# Modulo_Telemetros.net
KiCad netlist of a schematic drawn in Altium Designer
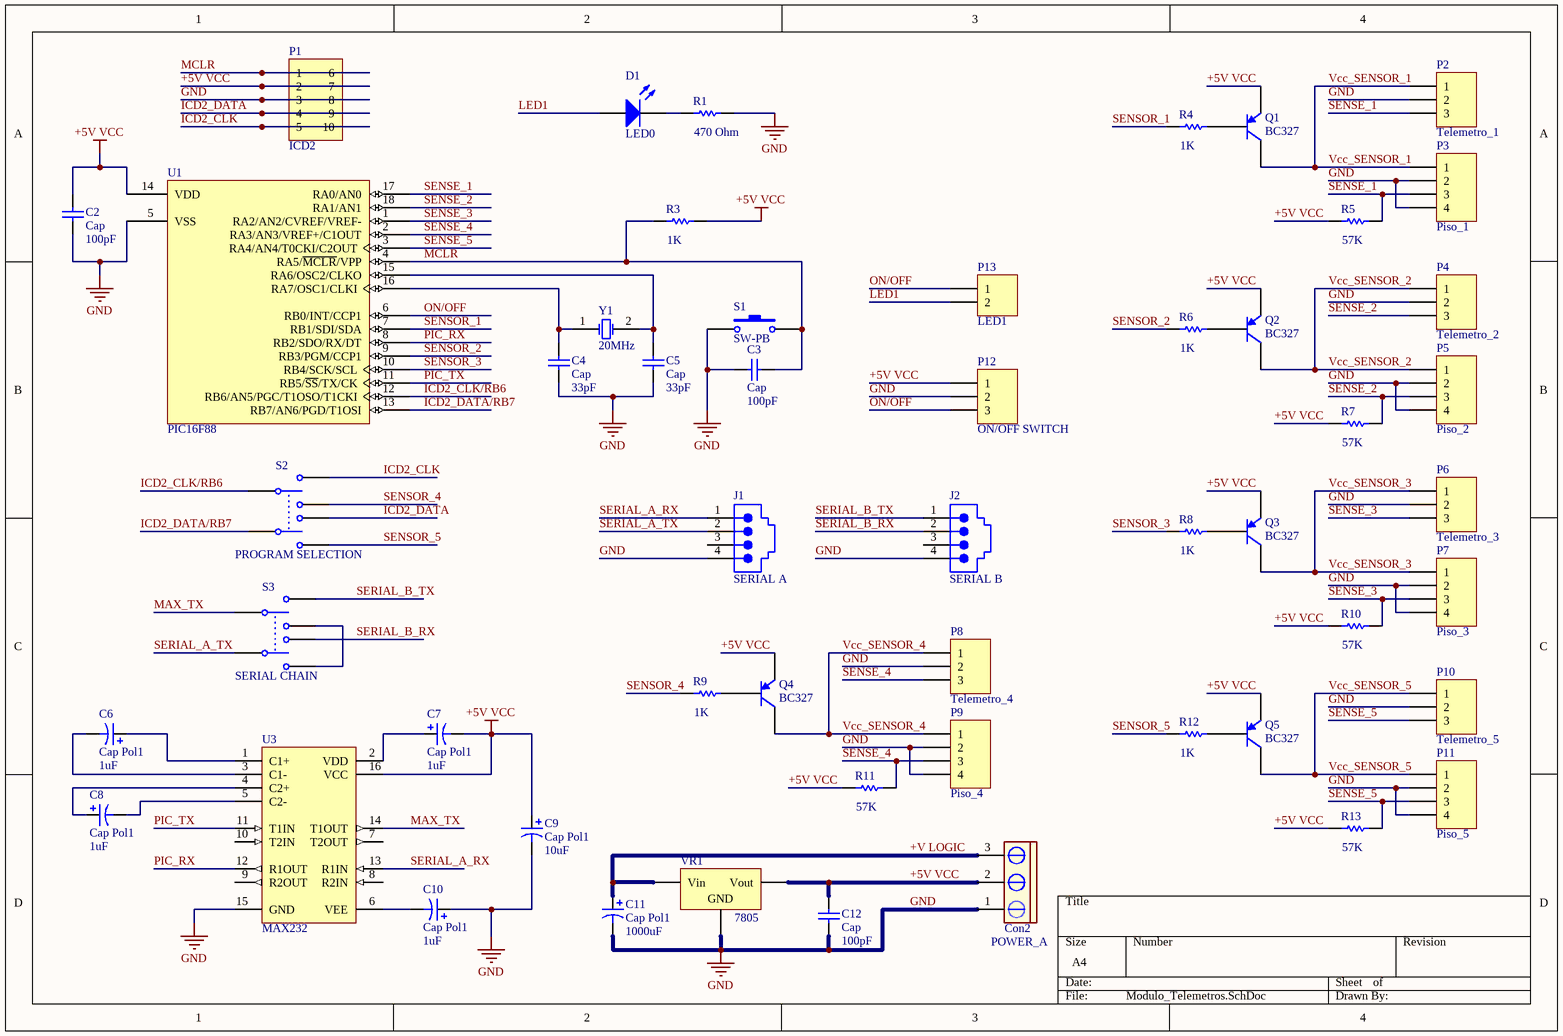
[diagram p0: Modulo_Telemetros.SchDoc]

(export (version "E")
  (design (tool "Eeschema 10.0.6"))
  (components
    (comp (ref "C2")
      (value "Cap")
      (footprint "CAPR2.54-5.1x3.2")
      (description "Capacitor")
      (fields (field (name "ALTIUM_VALUE") "100pF") (field (name "PUBLISHER") "Altium Limited"))
      (libsource (lib "Miscellaneous Devices") (part "Cap"))
    )
    (comp (ref "C3")
      (value "Cap")
      (footprint "CAPR2.54-5.1x3.2")
      (description "Capacitor")
      (fields (field (name "ALTIUM_VALUE") "100pF") (field (name "PUBLISHER") "Altium Limited"))
      (libsource (lib "Miscellaneous Devices") (part "Cap"))
    )
    (comp (ref "C4")
      (value "Cap")
      (footprint "CAPR2.54-5.1x3.2")
      (description "Capacitor")
      (fields (field (name "ALTIUM_VALUE") "33pF") (field (name "PUBLISHER") "Altium Limited"))
      (libsource (lib "Miscellaneous Devices") (part "Cap"))
    )
    (comp (ref "C5")
      (value "Cap")
      (footprint "CAPR2.54-5.1x3.2")
      (description "Capacitor")
      (fields (field (name "ALTIUM_VALUE") "33pF") (field (name "PUBLISHER") "Altium Limited"))
      (libsource (lib "Miscellaneous Devices") (part "Cap"))
    )
    (comp (ref "C6")
      (value "Cap Pol1")
      (footprint "CAPPR2-5x6.8")
      (description "Polarized Capacitor (Radial)")
      (fields (field (name "ALTIUM_VALUE") "1uF") (field (name "PUBLISHER") "Altium Limited"))
      (libsource (lib "Miscellaneous Devices") (part "Cap Pol1"))
    )
    (comp (ref "C7")
      (value "Cap Pol1")
      (footprint "CAPPR2-5x6.8")
      (description "Polarized Capacitor (Radial)")
      (fields (field (name "ALTIUM_VALUE") "1uF") (field (name "PUBLISHER") "Altium Limited"))
      (libsource (lib "Miscellaneous Devices") (part "Cap Pol1"))
    )
    (comp (ref "C8")
      (value "Cap Pol1")
      (footprint "CAPPR2-5x6.8")
      (description "Polarized Capacitor (Radial)")
      (fields (field (name "ALTIUM_VALUE") "1uF") (field (name "PUBLISHER") "Altium Limited"))
      (libsource (lib "Miscellaneous Devices") (part "Cap Pol1"))
    )
    (comp (ref "C9")
      (value "Cap Pol1")
      (footprint "CAPPR2-5x6.8")
      (description "Polarized Capacitor (Radial)")
      (fields (field (name "ALTIUM_VALUE") "10uF") (field (name "PUBLISHER") "Altium Limited"))
      (libsource (lib "Miscellaneous Devices") (part "Cap Pol1"))
    )
    (comp (ref "C10")
      (value "Cap Pol1")
      (footprint "CAPPR2-5x6.8")
      (description "Polarized Capacitor (Radial)")
      (fields (field (name "ALTIUM_VALUE") "1uF") (field (name "PUBLISHER") "Altium Limited"))
      (libsource (lib "Miscellaneous Devices") (part "Cap Pol1"))
    )
    (comp (ref "C11")
      (value "Cap Pol1")
      (footprint "RB5-10.5")
      (description "Polarized Capacitor (Radial)")
      (fields (field (name "ALTIUM_VALUE") "1000uF") (field (name "PUBLISHER") "Altium Limited"))
      (libsource (lib "Miscellaneous Devices") (part "Cap Pol1"))
    )
    (comp (ref "C12")
      (value "Cap")
      (footprint "CAPR2.54-5.1x3.2")
      (description "Capacitor")
      (fields (field (name "ALTIUM_VALUE") "100pF") (field (name "PUBLISHER") "Altium Limited"))
      (libsource (lib "Miscellaneous Devices") (part "Cap"))
    )
    (comp (ref "Con2")
      (value "POWER_A")
      (footprint "My_CN3")
      (description "Connector green screw")
      (libsource (lib "Protel_Library") (part "CON3 pin Green"))
    )
    (comp (ref "D1")
      (value "LED0")
      (footprint "LED-0")
      (description "Typical INFRARED GaAs LED")
      (fields (field (name "PUBLISHER") "Altium Limited"))
      (libsource (lib "Miscellaneous Devices") (part "LED0"))
    )
    (comp (ref "J1")
      (value "SERIAL A")
      (footprint "15-43-6245")
      (description "Right Angle, Standard Profile, RJ45-Keyed, Flange Mount PCB Jack")
      (fields (field (name "PUBLISHER") "Altium Limited"))
      (libsource (lib "Molex Modular Jack Right Angle") (part "15-43-6245"))
    )
    (comp (ref "J2")
      (value "SERIAL B")
      (footprint "15-43-6245")
      (description "Right Angle, Standard Profile, RJ45-Keyed, Flange Mount PCB Jack")
      (fields (field (name "PUBLISHER") "Altium Limited"))
      (libsource (lib "Molex Modular Jack Right Angle") (part "15-43-6245"))
    )
    (comp (ref "P1")
      (value "ICD2")
      (footprint "HEADER10_5x2_B")
      (description "Header, 5-Pin, Dual row")
      (fields (field (name "PUBLISHER") "Altium Limited"))
      (libsource (lib "Miscellaneous Connectors") (part "Header 5X2A"))
    )
    (comp (ref "P2")
      (value "Telemetro_1")
      (footprint "HDR1X3")
      (description "Header, 3-Pin")
      (fields (field (name "PUBLISHER") "Altium Limited"))
      (libsource (lib "Miscellaneous Connectors") (part "Header 3"))
    )
    (comp (ref "P3")
      (value "Piso_1")
      (footprint "HDR1X4")
      (description "Header, 4-Pin")
      (fields (field (name "PUBLISHER") "Altium Limited"))
      (libsource (lib "Miscellaneous Connectors") (part "Header 4"))
    )
    (comp (ref "P4")
      (value "Telemetro_2")
      (footprint "HDR1X3")
      (description "Header, 3-Pin")
      (fields (field (name "PUBLISHER") "Altium Limited"))
      (libsource (lib "Miscellaneous Connectors") (part "Header 3"))
    )
    (comp (ref "P5")
      (value "Piso_2")
      (footprint "HDR1X4")
      (description "Header, 4-Pin")
      (fields (field (name "PUBLISHER") "Altium Limited"))
      (libsource (lib "Miscellaneous Connectors") (part "Header 4"))
    )
    (comp (ref "P6")
      (value "Telemetro_3")
      (footprint "HDR1X3")
      (description "Header, 3-Pin")
      (fields (field (name "PUBLISHER") "Altium Limited"))
      (libsource (lib "Miscellaneous Connectors") (part "Header 3"))
    )
    (comp (ref "P7")
      (value "Piso_3")
      (footprint "HDR1X4")
      (description "Header, 4-Pin")
      (fields (field (name "PUBLISHER") "Altium Limited"))
      (libsource (lib "Miscellaneous Connectors") (part "Header 4"))
    )
    (comp (ref "P8")
      (value "Telemetro_4")
      (footprint "HDR1X3")
      (description "Header, 3-Pin")
      (fields (field (name "PUBLISHER") "Altium Limited"))
      (libsource (lib "Miscellaneous Connectors") (part "Header 3"))
    )
    (comp (ref "P9")
      (value "Piso_4")
      (footprint "HDR1X4")
      (description "Header, 4-Pin")
      (fields (field (name "PUBLISHER") "Altium Limited"))
      (libsource (lib "Miscellaneous Connectors") (part "Header 4"))
    )
    (comp (ref "P10")
      (value "Telemetro_5")
      (footprint "HDR1X3")
      (description "Header, 3-Pin")
      (fields (field (name "PUBLISHER") "Altium Limited"))
      (libsource (lib "Miscellaneous Connectors") (part "Header 3"))
    )
    (comp (ref "P11")
      (value "Piso_5")
      (footprint "HDR1X4")
      (description "Header, 4-Pin")
      (fields (field (name "PUBLISHER") "Altium Limited"))
      (libsource (lib "Miscellaneous Connectors") (part "Header 4"))
    )
    (comp (ref "P12")
      (value "ON/OFF SWITCH")
      (footprint "HDR1X3")
      (description "Header, 3-Pin")
      (fields (field (name "PUBLISHER") "Altium Limited"))
      (libsource (lib "Miscellaneous Connectors") (part "Header 3"))
    )
    (comp (ref "P13")
      (value "LED1")
      (footprint "HDR1X2")
      (description "Header, 2-Pin")
      (fields (field (name "PUBLISHER") "Altium Limited"))
      (libsource (lib "Miscellaneous Connectors") (part "Header 2"))
    )
    (comp (ref "Q1")
      (value "BC327")
      (footprint "TO-92A")
      (description "PNP Switching Transistor")
      (fields (field (name "PUBLISHER") "Altium Limited"))
      (libsource (lib "FSC Discrete BJT") (part "2N5771"))
    )
    (comp (ref "Q2")
      (value "BC327")
      (footprint "TO-92A")
      (description "PNP Switching Transistor")
      (fields (field (name "PUBLISHER") "Altium Limited"))
      (libsource (lib "FSC Discrete BJT") (part "2N5771"))
    )
    (comp (ref "Q3")
      (value "BC327")
      (footprint "TO-92A")
      (description "PNP Switching Transistor")
      (fields (field (name "PUBLISHER") "Altium Limited"))
      (libsource (lib "FSC Discrete BJT") (part "2N5771"))
    )
    (comp (ref "Q4")
      (value "BC327")
      (footprint "TO-92A")
      (description "PNP Switching Transistor")
      (fields (field (name "PUBLISHER") "Altium Limited"))
      (libsource (lib "FSC Discrete BJT") (part "2N5771"))
    )
    (comp (ref "Q5")
      (value "BC327")
      (footprint "TO-92A")
      (description "PNP Switching Transistor")
      (fields (field (name "PUBLISHER") "Altium Limited"))
      (libsource (lib "FSC Discrete BJT") (part "2N5771"))
    )
    (comp (ref "R1")
      (value "470 Ohm")
      (footprint "AXIAL-0.3")
      (description "Resistor")
      (fields (field (name "Comment") "Res1") (field (name "PUBLISHER") "Altium Limited"))
      (libsource (lib "Miscellaneous Devices") (part "Res1"))
    )
    (comp (ref "R3")
      (value "1K")
      (footprint "AXIAL-0.3")
      (description "Resistor")
      (fields (field (name "Comment") "Res1") (field (name "PUBLISHER") "Altium Limited"))
      (libsource (lib "Miscellaneous Devices") (part "Res1"))
    )
    (comp (ref "R4")
      (value "1K")
      (footprint "AXIAL-0.3")
      (description "Resistor")
      (fields (field (name "Comment") "Res1") (field (name "PUBLISHER") "Altium Limited"))
      (libsource (lib "Miscellaneous Devices") (part "Res1"))
    )
    (comp (ref "R5")
      (value "57K")
      (footprint "AXIAL-0.3")
      (description "Resistor")
      (fields (field (name "Comment") "Res1") (field (name "PUBLISHER") "Altium Limited"))
      (libsource (lib "Miscellaneous Devices") (part "Res1"))
    )
    (comp (ref "R6")
      (value "1K")
      (footprint "AXIAL-0.3")
      (description "Resistor")
      (fields (field (name "Comment") "Res1") (field (name "PUBLISHER") "Altium Limited"))
      (libsource (lib "Miscellaneous Devices") (part "Res1"))
    )
    (comp (ref "R7")
      (value "57K")
      (footprint "AXIAL-0.3")
      (description "Resistor")
      (fields (field (name "Comment") "Res1") (field (name "PUBLISHER") "Altium Limited"))
      (libsource (lib "Miscellaneous Devices") (part "Res1"))
    )
    (comp (ref "R8")
      (value "1K")
      (footprint "AXIAL-0.3")
      (description "Resistor")
      (fields (field (name "Comment") "Res1") (field (name "PUBLISHER") "Altium Limited"))
      (libsource (lib "Miscellaneous Devices") (part "Res1"))
    )
    (comp (ref "R9")
      (value "1K")
      (footprint "AXIAL-0.3")
      (description "Resistor")
      (fields (field (name "Comment") "Res1") (field (name "PUBLISHER") "Altium Limited"))
      (libsource (lib "Miscellaneous Devices") (part "Res1"))
    )
    (comp (ref "R10")
      (value "57K")
      (footprint "AXIAL-0.3")
      (description "Resistor")
      (fields (field (name "Comment") "Res1") (field (name "PUBLISHER") "Altium Limited"))
      (libsource (lib "Miscellaneous Devices") (part "Res1"))
    )
    (comp (ref "R11")
      (value "57K")
      (footprint "AXIAL-0.3")
      (description "Resistor")
      (fields (field (name "Comment") "Res1") (field (name "PUBLISHER") "Altium Limited"))
      (libsource (lib "Miscellaneous Devices") (part "Res1"))
    )
    (comp (ref "R12")
      (value "1K")
      (footprint "AXIAL-0.3")
      (description "Resistor")
      (fields (field (name "Comment") "Res1") (field (name "PUBLISHER") "Altium Limited"))
      (libsource (lib "Miscellaneous Devices") (part "Res1"))
    )
    (comp (ref "R13")
      (value "57K")
      (footprint "AXIAL-0.3")
      (description "Resistor")
      (fields (field (name "Comment") "Res1") (field (name "PUBLISHER") "Altium Limited"))
      (libsource (lib "Miscellaneous Devices") (part "Res1"))
    )
    (comp (ref "S1")
      (value "SW-PB")
      (footprint "TS-063")
      (description "Switch")
      (fields (field (name "PUBLISHER") "Altium Limited"))
      (libsource (lib "Miscellaneous Devices") (part "SW-PB"))
    )
    (comp (ref "S2")
      (value "PROGRAM SELECTION")
      (footprint "LD-202mini")
      (description "Double-Pole, Double-Throw Switch")
      (fields (field (name "PUBLISHER") "Altium Limited"))
      (libsource (lib "Miscellaneous Devices") (part "SW-DPDT"))
    )
    (comp (ref "S3")
      (value "SERIAL CHAIN")
      (footprint "LD-202mini")
      (description "Double-Pole, Double-Throw Switch")
      (fields (field (name "PUBLISHER") "Altium Limited"))
      (libsource (lib "Miscellaneous Devices") (part "SW-DPDT"))
    )
    (comp (ref "U1")
      (value "PIC16F88")
      (footprint "PDIP300-P18")
      (fields (field (name "PUBLISHER") "Altium Limited"))
      (libsource (lib "Microchip Microcontroller 8-Bit PIC16") (part "PIC16F88-E/P"))
    )
    (comp (ref "U3")
      (value "MAX232")
      (footprint "PE16A")
      (description "+5V Powered, Multi-Channel RS-232 Driver/Receiver")
      (fields (field (name "PUBLISHER") "Altium Limited"))
      (libsource (lib "Maxim Communication Transceiver") (part "MAX232ACPE"))
    )
    (comp (ref "VR1")
      (value "7805")
      (footprint "My_TO-220")
      (description "Voltage Regulator")
      (fields (field (name "PUBLISHER") "Altium Limited"))
      (libsource (lib "Miscellaneous Devices") (part "Volt Reg"))
    )
    (comp (ref "Y1")
      (value "20MHz")
      (footprint "My_Crystal")
      (description "Crystal Oscillator")
      (fields (field (name "PUBLISHER") "Altium Limited"))
      (libsource (lib "Miscellaneous Devices") (part "XTAL"))
    )
  )
  (nets
    (net (code "1") (name "+5V VCC") (class "Default")
      (node (ref "C12") (pin "2") (pinfunction "2_2") (pintype "passive"))
      (node (ref "C2") (pin "2") (pinfunction "2_2") (pintype "passive"))
      (node (ref "C7") (pin "2") (pinfunction "2_2") (pintype "passive"))
      (node (ref "C9") (pin "1") (pinfunction "1_1") (pintype "passive"))
      (node (ref "Con2") (pin "2") (pinfunction "2_2") (pintype "passive"))
      (node (ref "P1") (pin "2") (pinfunction "2_2") (pintype "passive"))
      (node (ref "P1") (pin "7") (pinfunction "7_7") (pintype "passive"))
      (node (ref "P12") (pin "1") (pinfunction "1_1") (pintype "passive"))
      (node (ref "Q1") (pin "1") (pinfunction "E_1") (pintype "passive"))
      (node (ref "Q2") (pin "1") (pinfunction "E_1") (pintype "passive"))
      (node (ref "Q3") (pin "1") (pinfunction "E_1") (pintype "passive"))
      (node (ref "Q4") (pin "1") (pinfunction "E_1") (pintype "passive"))
      (node (ref "Q5") (pin "1") (pinfunction "E_1") (pintype "passive"))
      (node (ref "R10") (pin "1") (pinfunction "1_1") (pintype "passive"))
      (node (ref "R11") (pin "1") (pinfunction "1_1") (pintype "passive"))
      (node (ref "R13") (pin "1") (pinfunction "1_1") (pintype "passive"))
      (node (ref "R3") (pin "2") (pinfunction "2_2") (pintype "passive"))
      (node (ref "R5") (pin "1") (pinfunction "1_1") (pintype "passive"))
      (node (ref "R7") (pin "1") (pinfunction "1_1") (pintype "passive"))
      (node (ref "U1") (pin "14") (pinfunction "VDD_14") (pintype "power_in"))
      (node (ref "U3") (pin "16") (pinfunction "VCC_16") (pintype "power_in"))
      (node (ref "VR1") (pin "3") (pinfunction "Vout_3") (pintype "passive"))
    )
    (net (code "2") (name "/+V LOGIC") (class "Default")
      (node (ref "C11") (pin "1") (pinfunction "1_1") (pintype "passive"))
      (node (ref "Con2") (pin "3") (pinfunction "3_3") (pintype "passive"))
      (node (ref "VR1") (pin "1") (pinfunction "Vin_1") (pintype "passive"))
    )
    (net (code "3") (name "/ICD2_CLK") (class "Default")
      (node (ref "P1") (pin "10") (pinfunction "10_10") (pintype "passive"))
      (node (ref "P1") (pin "5") (pinfunction "5_5") (pintype "passive"))
      (node (ref "S2") (pin "2") (pinfunction "2_2") (pintype "passive"))
    )
    (net (code "4") (name "/ICD2_CLK{slash}RB6") (class "Default")
      (node (ref "S2") (pin "1") (pinfunction "1_1") (pintype "passive"))
      (node (ref "U1") (pin "12") (pinfunction "RB6/AN5/PGC/T1OSO/T1CKI_12") (pintype "bidirectional"))
    )
    (net (code "5") (name "/ICD2_DATA") (class "Default")
      (node (ref "P1") (pin "4") (pinfunction "4_4") (pintype "passive"))
      (node (ref "P1") (pin "9") (pinfunction "9_9") (pintype "passive"))
      (node (ref "S2") (pin "5") (pinfunction "5_5") (pintype "passive"))
    )
    (net (code "6") (name "/ICD2_DATA{slash}RB7") (class "Default")
      (node (ref "S2") (pin "4") (pinfunction "4_4") (pintype "passive"))
      (node (ref "U1") (pin "13") (pinfunction "RB7/AN6/PGD/T1OSI_13") (pintype "bidirectional"))
    )
    (net (code "7") (name "/LED1") (class "Default")
      (node (ref "D1") (pin "1") (pinfunction "A_1") (pintype "passive"))
      (node (ref "P13") (pin "2") (pinfunction "2_2") (pintype "passive"))
    )
    (net (code "8") (name "/MAX_TX") (class "Default")
      (node (ref "S3") (pin "1") (pinfunction "1_1") (pintype "passive"))
      (node (ref "U3") (pin "14") (pinfunction "T1OUT_14") (pintype "output"))
    )
    (net (code "9") (name "/MCLR") (class "Default")
      (node (ref "C3") (pin "2") (pinfunction "2_2") (pintype "passive"))
      (node (ref "P1") (pin "1") (pinfunction "1_1") (pintype "passive"))
      (node (ref "P1") (pin "6") (pinfunction "6_6") (pintype "passive"))
      (node (ref "R3") (pin "1") (pinfunction "1_1") (pintype "passive"))
      (node (ref "S1") (pin "2") (pinfunction "2_2") (pintype "passive"))
      (node (ref "U1") (pin "4") (pinfunction "RA5/~{MCLR}/VPP_4") (pintype "bidirectional"))
    )
    (net (code "10") (name "/ON{slash}OFF") (class "Default")
      (node (ref "P12") (pin "3") (pinfunction "3_3") (pintype "passive"))
      (node (ref "P13") (pin "1") (pinfunction "1_1") (pintype "passive"))
      (node (ref "U1") (pin "6") (pinfunction "RB0/INT/CCP1_6") (pintype "bidirectional"))
    )
    (net (code "11") (name "/PIC_RX") (class "Default")
      (node (ref "U1") (pin "8") (pinfunction "RB2/SDO/RX/DT_8") (pintype "bidirectional"))
      (node (ref "U3") (pin "12") (pinfunction "R1OUT_12") (pintype "output"))
    )
    (net (code "12") (name "/PIC_TX") (class "Default")
      (node (ref "U1") (pin "11") (pinfunction "RB5/~{SS}/TX/CK_11") (pintype "bidirectional"))
      (node (ref "U3") (pin "11") (pinfunction "T1IN_11") (pintype "input"))
    )
    (net (code "13") (name "/SENSE_1") (class "Default")
      (node (ref "P2") (pin "3") (pinfunction "3_3") (pintype "passive"))
      (node (ref "P3") (pin "3") (pinfunction "3_3") (pintype "passive"))
      (node (ref "R5") (pin "2") (pinfunction "2_2") (pintype "passive"))
      (node (ref "U1") (pin "17") (pinfunction "RA0/AN0_17") (pintype "bidirectional"))
    )
    (net (code "14") (name "/SENSE_2") (class "Default")
      (node (ref "P4") (pin "3") (pinfunction "3_3") (pintype "passive"))
      (node (ref "P5") (pin "3") (pinfunction "3_3") (pintype "passive"))
      (node (ref "R7") (pin "2") (pinfunction "2_2") (pintype "passive"))
      (node (ref "U1") (pin "18") (pinfunction "RA1/AN1_18") (pintype "bidirectional"))
    )
    (net (code "15") (name "/SENSE_3") (class "Default")
      (node (ref "P6") (pin "3") (pinfunction "3_3") (pintype "passive"))
      (node (ref "P7") (pin "3") (pinfunction "3_3") (pintype "passive"))
      (node (ref "R10") (pin "2") (pinfunction "2_2") (pintype "passive"))
      (node (ref "U1") (pin "1") (pinfunction "RA2/AN2/CVREF/VREF-_1") (pintype "bidirectional"))
    )
    (net (code "16") (name "/SENSE_4") (class "Default")
      (node (ref "P8") (pin "3") (pinfunction "3_3") (pintype "passive"))
      (node (ref "P9") (pin "3") (pinfunction "3_3") (pintype "passive"))
      (node (ref "R11") (pin "2") (pinfunction "2_2") (pintype "passive"))
      (node (ref "U1") (pin "2") (pinfunction "RA3/AN3/VREF+/C1OUT_2") (pintype "bidirectional"))
    )
    (net (code "17") (name "/SENSE_5") (class "Default")
      (node (ref "P10") (pin "3") (pinfunction "3_3") (pintype "passive"))
      (node (ref "P11") (pin "3") (pinfunction "3_3") (pintype "passive"))
      (node (ref "R13") (pin "2") (pinfunction "2_2") (pintype "passive"))
      (node (ref "U1") (pin "3") (pinfunction "RA4/AN4/T0CKI/C2OUT_3") (pintype "bidirectional"))
    )
    (net (code "18") (name "/SENSOR_1") (class "Default")
      (node (ref "R4") (pin "1") (pinfunction "1_1") (pintype "passive"))
      (node (ref "U1") (pin "7") (pinfunction "RB1/SDI/SDA_7") (pintype "bidirectional"))
    )
    (net (code "19") (name "/SENSOR_2") (class "Default")
      (node (ref "R6") (pin "1") (pinfunction "1_1") (pintype "passive"))
      (node (ref "U1") (pin "9") (pinfunction "RB3/PGM/CCP1_9") (pintype "bidirectional"))
    )
    (net (code "20") (name "/SENSOR_3") (class "Default")
      (node (ref "R8") (pin "1") (pinfunction "1_1") (pintype "passive"))
      (node (ref "U1") (pin "10") (pinfunction "RB4/SCK/SCL_10") (pintype "bidirectional"))
    )
    (net (code "21") (name "/SENSOR_4") (class "Default")
      (node (ref "R9") (pin "1") (pinfunction "1_1") (pintype "passive"))
      (node (ref "S2") (pin "3") (pinfunction "3_3") (pintype "passive"))
    )
    (net (code "22") (name "/SENSOR_5") (class "Default")
      (node (ref "R12") (pin "1") (pinfunction "1_1") (pintype "passive"))
      (node (ref "S2") (pin "6") (pinfunction "6_6") (pintype "passive"))
    )
    (net (code "23") (name "/SERIAL_A_RX") (class "Default")
      (node (ref "J1") (pin "1") (pinfunction "1_1") (pintype "passive"))
      (node (ref "U3") (pin "13") (pinfunction "R1IN_13") (pintype "input"))
    )
    (net (code "24") (name "/SERIAL_A_TX") (class "Default")
      (node (ref "J1") (pin "2") (pinfunction "2_2") (pintype "passive"))
      (node (ref "S3") (pin "4") (pinfunction "4_4") (pintype "passive"))
    )
    (net (code "25") (name "/SERIAL_B_RX") (class "Default")
      (node (ref "J2") (pin "2") (pinfunction "2_2") (pintype "passive"))
      (node (ref "S3") (pin "5") (pinfunction "5_5") (pintype "passive"))
    )
    (net (code "26") (name "/SERIAL_B_TX") (class "Default")
      (node (ref "J2") (pin "1") (pinfunction "1_1") (pintype "passive"))
      (node (ref "S3") (pin "2") (pinfunction "2_2") (pintype "passive"))
    )
    (net (code "27") (name "/Vcc_SENSOR_1") (class "Default")
      (node (ref "P2") (pin "1") (pinfunction "1_1") (pintype "passive"))
      (node (ref "P3") (pin "1") (pinfunction "1_1") (pintype "passive"))
      (node (ref "Q1") (pin "3") (pinfunction "C_3") (pintype "passive"))
    )
    (net (code "28") (name "/Vcc_SENSOR_2") (class "Default")
      (node (ref "P4") (pin "1") (pinfunction "1_1") (pintype "passive"))
      (node (ref "P5") (pin "1") (pinfunction "1_1") (pintype "passive"))
      (node (ref "Q2") (pin "3") (pinfunction "C_3") (pintype "passive"))
    )
    (net (code "29") (name "/Vcc_SENSOR_3") (class "Default")
      (node (ref "P6") (pin "1") (pinfunction "1_1") (pintype "passive"))
      (node (ref "P7") (pin "1") (pinfunction "1_1") (pintype "passive"))
      (node (ref "Q3") (pin "3") (pinfunction "C_3") (pintype "passive"))
    )
    (net (code "30") (name "/Vcc_SENSOR_4") (class "Default")
      (node (ref "P8") (pin "1") (pinfunction "1_1") (pintype "passive"))
      (node (ref "P9") (pin "1") (pinfunction "1_1") (pintype "passive"))
      (node (ref "Q4") (pin "3") (pinfunction "C_3") (pintype "passive"))
    )
    (net (code "31") (name "/Vcc_SENSOR_5") (class "Default")
      (node (ref "P10") (pin "1") (pinfunction "1_1") (pintype "passive"))
      (node (ref "P11") (pin "1") (pinfunction "1_1") (pintype "passive"))
      (node (ref "Q5") (pin "3") (pinfunction "C_3") (pintype "passive"))
    )
    (net (code "32") (name "GND") (class "Default")
      (node (ref "C10") (pin "1") (pinfunction "1_1") (pintype "passive"))
      (node (ref "C11") (pin "2") (pinfunction "2_2") (pintype "passive"))
      (node (ref "C12") (pin "1") (pinfunction "1_1") (pintype "passive"))
      (node (ref "C2") (pin "1") (pinfunction "1_1") (pintype "passive"))
      (node (ref "C3") (pin "1") (pinfunction "1_1") (pintype "passive"))
      (node (ref "C4") (pin "1") (pinfunction "1_1") (pintype "passive"))
      (node (ref "C5") (pin "1") (pinfunction "1_1") (pintype "passive"))
      (node (ref "C9") (pin "2") (pinfunction "2_2") (pintype "passive"))
      (node (ref "Con2") (pin "1") (pinfunction "1_1") (pintype "passive"))
      (node (ref "J1") (pin "4") (pinfunction "4_4") (pintype "passive"))
      (node (ref "J2") (pin "4") (pinfunction "4_4") (pintype "passive"))
      (node (ref "P1") (pin "3") (pinfunction "3_3") (pintype "passive"))
      (node (ref "P1") (pin "8") (pinfunction "8_8") (pintype "passive"))
      (node (ref "P10") (pin "2") (pinfunction "2_2") (pintype "passive"))
      (node (ref "P11") (pin "2") (pinfunction "2_2") (pintype "passive"))
      (node (ref "P11") (pin "4") (pinfunction "4_4") (pintype "passive"))
      (node (ref "P12") (pin "2") (pinfunction "2_2") (pintype "passive"))
      (node (ref "P2") (pin "2") (pinfunction "2_2") (pintype "passive"))
      (node (ref "P3") (pin "2") (pinfunction "2_2") (pintype "passive"))
      (node (ref "P3") (pin "4") (pinfunction "4_4") (pintype "passive"))
      (node (ref "P4") (pin "2") (pinfunction "2_2") (pintype "passive"))
      (node (ref "P5") (pin "2") (pinfunction "2_2") (pintype "passive"))
      (node (ref "P5") (pin "4") (pinfunction "4_4") (pintype "passive"))
      (node (ref "P6") (pin "2") (pinfunction "2_2") (pintype "passive"))
      (node (ref "P7") (pin "2") (pinfunction "2_2") (pintype "passive"))
      (node (ref "P7") (pin "4") (pinfunction "4_4") (pintype "passive"))
      (node (ref "P8") (pin "2") (pinfunction "2_2") (pintype "passive"))
      (node (ref "P9") (pin "2") (pinfunction "2_2") (pintype "passive"))
      (node (ref "P9") (pin "4") (pinfunction "4_4") (pintype "passive"))
      (node (ref "R1") (pin "2") (pinfunction "2_2") (pintype "passive"))
      (node (ref "S1") (pin "1") (pinfunction "1_1") (pintype "passive"))
      (node (ref "U1") (pin "5") (pinfunction "VSS_5") (pintype "power_in"))
      (node (ref "U3") (pin "15") (pinfunction "GND_15") (pintype "power_in"))
      (node (ref "VR1") (pin "2") (pinfunction "GND_2") (pintype "passive"))
    )
    (net (code "33") (name "Net-(D1-K)") (class "Default")
      (node (ref "D1") (pin "2") (pinfunction "K_2") (pintype "passive"))
      (node (ref "R1") (pin "1") (pinfunction "1_1") (pintype "passive"))
    )
    (net (code "34") (name "Net-(Q1-B)") (class "Default")
      (node (ref "Q1") (pin "2") (pinfunction "B_2") (pintype "passive"))
      (node (ref "R4") (pin "2") (pinfunction "2_2") (pintype "passive"))
    )
    (net (code "35") (name "Net-(Q2-B)") (class "Default")
      (node (ref "Q2") (pin "2") (pinfunction "B_2") (pintype "passive"))
      (node (ref "R6") (pin "2") (pinfunction "2_2") (pintype "passive"))
    )
    (net (code "36") (name "Net-(Q3-B)") (class "Default")
      (node (ref "Q3") (pin "2") (pinfunction "B_2") (pintype "passive"))
      (node (ref "R8") (pin "2") (pinfunction "2_2") (pintype "passive"))
    )
    (net (code "37") (name "Net-(Q4-B)") (class "Default")
      (node (ref "Q4") (pin "2") (pinfunction "B_2") (pintype "passive"))
      (node (ref "R9") (pin "2") (pinfunction "2_2") (pintype "passive"))
    )
    (net (code "38") (name "Net-(Q5-B)") (class "Default")
      (node (ref "Q5") (pin "2") (pinfunction "B_2") (pintype "passive"))
      (node (ref "R12") (pin "2") (pinfunction "2_2") (pintype "passive"))
    )
    (net (code "39") (name "Net-(S3-Pad3)") (class "Default")
      (node (ref "S3") (pin "3") (pinfunction "3_3") (pintype "passive"))
      (node (ref "S3") (pin "6") (pinfunction "6_6") (pintype "passive"))
    )
    (net (code "40") (name "Net-(U1-RA6{slash}OSC2{slash}CLKO)") (class "Default")
      (node (ref "C5") (pin "2") (pinfunction "2_2") (pintype "passive"))
      (node (ref "U1") (pin "15") (pinfunction "RA6/OSC2/CLKO_15") (pintype "bidirectional"))
      (node (ref "Y1") (pin "2") (pinfunction "OSC2_2") (pintype "passive"))
    )
    (net (code "41") (name "Net-(U1-RA7{slash}OSC1{slash}CLKI)") (class "Default")
      (node (ref "C4") (pin "2") (pinfunction "2_2") (pintype "passive"))
      (node (ref "U1") (pin "16") (pinfunction "RA7/OSC1/CLKI_16") (pintype "bidirectional"))
      (node (ref "Y1") (pin "1") (pinfunction "OSC1_1") (pintype "passive"))
    )
    (net (code "42") (name "Net-(U3-C1+)") (class "Default")
      (node (ref "C6") (pin "1") (pinfunction "1_1") (pintype "passive"))
      (node (ref "U3") (pin "1") (pinfunction "C1+_1") (pintype "passive"))
    )
    (net (code "43") (name "Net-(U3-C1-)") (class "Default")
      (node (ref "C6") (pin "2") (pinfunction "2_2") (pintype "passive"))
      (node (ref "U3") (pin "3") (pinfunction "C1-_3") (pintype "passive"))
    )
    (net (code "44") (name "Net-(U3-C2+)") (class "Default")
      (node (ref "C8") (pin "1") (pinfunction "1_1") (pintype "passive"))
      (node (ref "U3") (pin "4") (pinfunction "C2+_4") (pintype "passive"))
    )
    (net (code "45") (name "Net-(U3-C2-)") (class "Default")
      (node (ref "C8") (pin "2") (pinfunction "2_2") (pintype "passive"))
      (node (ref "U3") (pin "5") (pinfunction "C2-_5") (pintype "passive"))
    )
    (net (code "46") (name "Net-(U3-VDD)") (class "Default")
      (node (ref "C7") (pin "1") (pinfunction "1_1") (pintype "passive"))
      (node (ref "U3") (pin "2") (pinfunction "VDD_2") (pintype "power_in"))
    )
    (net (code "47") (name "Net-(U3-VEE)") (class "Default")
      (node (ref "C10") (pin "2") (pinfunction "2_2") (pintype "passive"))
      (node (ref "U3") (pin "6") (pinfunction "VEE_6") (pintype "power_in"))
    )
    (net (code "48") (name "unconnected-(J1-Pad3)") (class "Default")
      (node (ref "J1") (pin "3") (pinfunction "3_3") (pintype "passive"))
    )
    (net (code "49") (name "unconnected-(J2-Pad3)") (class "Default")
      (node (ref "J2") (pin "3") (pinfunction "3_3") (pintype "passive"))
    )
    (net (code "50") (name "unconnected-(U3-R2IN-Pad8)") (class "Default")
      (node (ref "U3") (pin "8") (pinfunction "R2IN_8") (pintype "input"))
    )
    (net (code "51") (name "unconnected-(U3-R2OUT-Pad9)") (class "Default")
      (node (ref "U3") (pin "9") (pinfunction "R2OUT_9") (pintype "output"))
    )
    (net (code "52") (name "unconnected-(U3-T2IN-Pad10)") (class "Default")
      (node (ref "U3") (pin "10") (pinfunction "T2IN_10") (pintype "input"))
    )
    (net (code "53") (name "unconnected-(U3-T2OUT-Pad7)") (class "Default")
      (node (ref "U3") (pin "7") (pinfunction "T2OUT_7") (pintype "output"))
    )
  )
)
